# walter.net
KiCad netlist of a schematic drawn in EAGLE
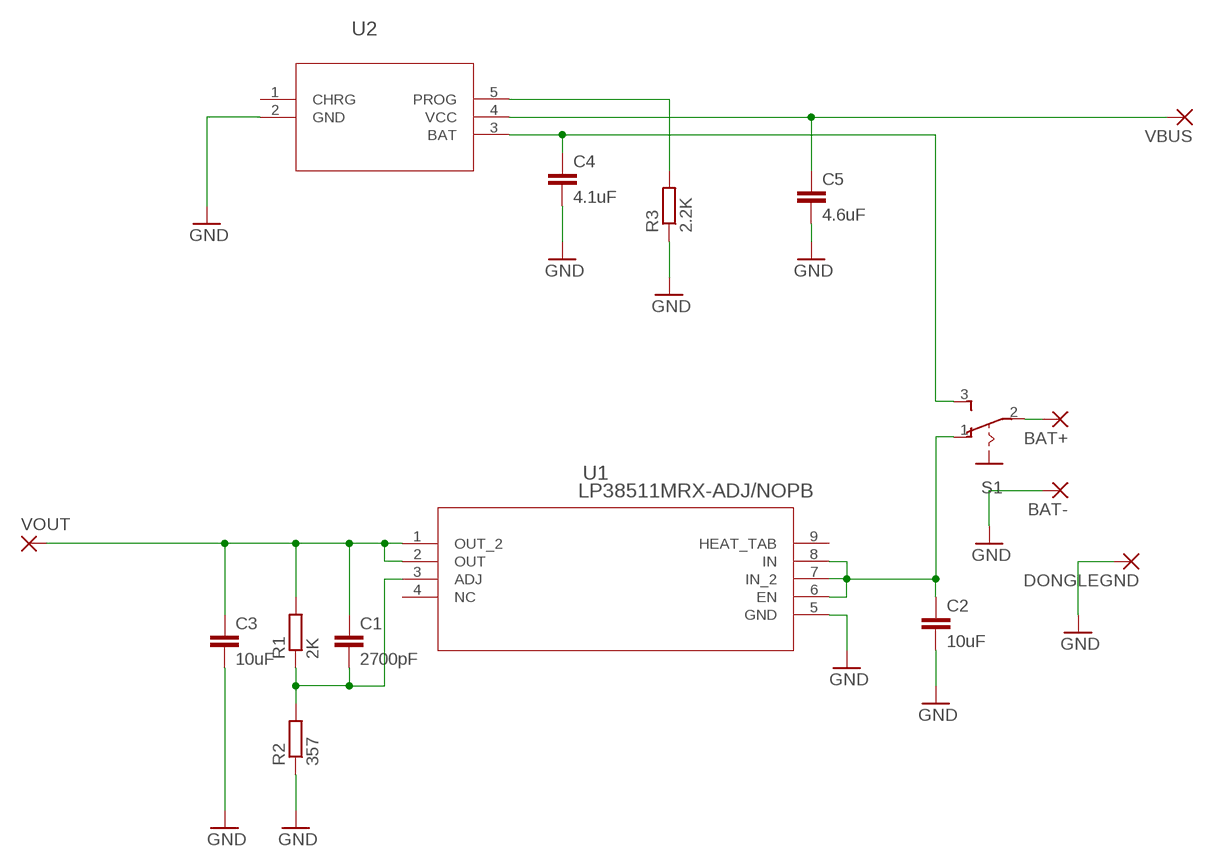
[diagram p0: schematic, sheet 1]

(export (version "E")
  (design (tool "Eeschema 10.0.6"))
  (components
    (comp (ref "BAT+")
      (value "1,6/0,8")
      (footprint "eagle-import:1,6_0,8")
      (libsource (lib "eagle-import") (part "1,6/0,8"))
    )
    (comp (ref "BAT-")
      (value "1,6/0,8")
      (footprint "eagle-import:1,6_0,8")
      (libsource (lib "eagle-import") (part "1,6/0,8"))
    )
    (comp (ref "C1")
      (value "2700pF")
      (footprint "eagle-import:C0402")
      (libsource (lib "eagle-import") (part "C-EUC0402"))
    )
    (comp (ref "C2")
      (value "10uF")
      (footprint "eagle-import:C0603")
      (libsource (lib "eagle-import") (part "C-EUC0603"))
    )
    (comp (ref "C3")
      (value "10uF")
      (footprint "eagle-import:C0603")
      (libsource (lib "eagle-import") (part "C-EUC0603"))
    )
    (comp (ref "C4")
      (value "4.1uF")
      (footprint "eagle-import:C0603")
      (libsource (lib "eagle-import") (part "C-EUC0603"))
    )
    (comp (ref "C5")
      (value "4.6uF")
      (footprint "eagle-import:C0603")
      (libsource (lib "eagle-import") (part "C-EUC0603"))
    )
    (comp (ref "DONGLEGND")
      (value "1,6/0,8")
      (footprint "eagle-import:1,6_0,8")
      (libsource (lib "eagle-import") (part "1,6/0,8"))
    )
    (comp (ref "R1")
      (value "2K")
      (footprint "eagle-import:R0402")
      (libsource (lib "eagle-import") (part "R-EU_R0402"))
    )
    (comp (ref "R2")
      (value "357")
      (footprint "eagle-import:R0603")
      (libsource (lib "eagle-import") (part "R-EU_R0603"))
    )
    (comp (ref "R3")
      (value "2.2K")
      (footprint "eagle-import:R0603")
      (libsource (lib "eagle-import") (part "R-EU_R0603"))
    )
    (comp (ref "S1")
      (value "255SB")
      (footprint "eagle-import:255SB")
      (libsource (lib "eagle-import") (part "255SB"))
    )
    (comp (ref "U1")
      (value "LP38511MRX-ADJ/NOPB")
      (footprint "eagle-import:MRA08B_TEX")
      (libsource (lib "eagle-import") (part "LP38511MRX-ADJ/NOPB"))
    )
    (comp (ref "U2")
      (value "LTC4054LES5-4.2TRPBF")
      (footprint "eagle-import:S_5_ADI")
      (fields
        (field (name "MANUFACTURER_PART_NUMBER") "LTC4054LES5-4.2#TRPBF")
        (field (name "COPYRIGHT") "Copyright (C) 2016 Accelerated Designs. All rights reserved")
      )
      (libsource (lib "eagle-import") (part "LTC4054LES5-4.2TRPBF"))
    )
    (comp (ref "VBUS")
      (value "1,6/0,8")
      (footprint "eagle-import:1,6_0,8")
      (libsource (lib "eagle-import") (part "1,6/0,8"))
    )
    (comp (ref "VOUT")
      (value "1,6/0,8")
      (footprint "eagle-import:1,6_0,8")
      (libsource (lib "eagle-import") (part "1,6/0,8"))
    )
  )
  (nets
    (net (code "1") (name "GND") (class "Default")
      (node (ref "BAT-") (pin "1") (pinfunction "P_1") (pintype "passive"))
      (node (ref "C2") (pin "2") (pinfunction "2_2") (pintype "passive"))
      (node (ref "C3") (pin "2") (pinfunction "2_2") (pintype "passive"))
      (node (ref "C4") (pin "2") (pinfunction "2_2") (pintype "passive"))
      (node (ref "C5") (pin "2") (pinfunction "2_2") (pintype "passive"))
      (node (ref "DONGLEGND") (pin "1") (pinfunction "P_1") (pintype "passive"))
      (node (ref "R2") (pin "1") (pinfunction "1_1") (pintype "passive"))
      (node (ref "R3") (pin "1") (pinfunction "1_1") (pintype "passive"))
      (node (ref "U1") (pin "5") (pinfunction "GND_5") (pintype "power_in"))
      (node (ref "U2") (pin "2") (pinfunction "GND_2") (pintype "passive"))
    )
    (net (code "2") (name "Net-(BAT+-P)") (class "Default")
      (node (ref "BAT+") (pin "1") (pinfunction "P_1") (pintype "passive"))
      (node (ref "S1") (pin "2") (pinfunction "P_2") (pintype "passive"))
    )
    (net (code "3") (name "Net-(S1-O)") (class "Default")
      (node (ref "C2") (pin "1") (pinfunction "1_1") (pintype "passive"))
      (node (ref "S1") (pin "1") (pinfunction "O_1") (pintype "passive"))
      (node (ref "U1") (pin "6") (pinfunction "EN_6") (pintype "input"))
      (node (ref "U1") (pin "7") (pinfunction "IN_2_7") (pintype "input"))
      (node (ref "U1") (pin "8") (pinfunction "IN_8") (pintype "input"))
    )
    (net (code "4") (name "Net-(S1-S)") (class "Default")
      (node (ref "C4") (pin "1") (pinfunction "1_1") (pintype "passive"))
      (node (ref "S1") (pin "3") (pinfunction "S_3") (pintype "passive"))
      (node (ref "U2") (pin "3") (pinfunction "BAT_3") (pintype "passive"))
    )
    (net (code "5") (name "Net-(U1-ADJ)") (class "Default")
      (node (ref "C1") (pin "2") (pinfunction "2_2") (pintype "passive"))
      (node (ref "R1") (pin "1") (pinfunction "1_1") (pintype "passive"))
      (node (ref "R2") (pin "2") (pinfunction "2_2") (pintype "passive"))
      (node (ref "U1") (pin "3") (pinfunction "ADJ_3") (pintype "passive"))
    )
    (net (code "6") (name "Net-(U1-OUT)") (class "Default")
      (node (ref "C1") (pin "1") (pinfunction "1_1") (pintype "passive"))
      (node (ref "C3") (pin "1") (pinfunction "1_1") (pintype "passive"))
      (node (ref "R1") (pin "2") (pinfunction "2_2") (pintype "passive"))
      (node (ref "U1") (pin "1") (pinfunction "OUT_2_1") (pintype "output"))
      (node (ref "U1") (pin "2") (pinfunction "OUT_2") (pintype "output"))
      (node (ref "VOUT") (pin "1") (pinfunction "P_1") (pintype "passive"))
    )
    (net (code "7") (name "Net-(U2-PROG)") (class "Default")
      (node (ref "R3") (pin "2") (pinfunction "2_2") (pintype "passive"))
      (node (ref "U2") (pin "5") (pinfunction "PROG_5") (pintype "passive"))
    )
    (net (code "8") (name "Net-(U2-VCC)") (class "Default")
      (node (ref "C5") (pin "1") (pinfunction "1_1") (pintype "passive"))
      (node (ref "U2") (pin "4") (pinfunction "VCC_4") (pintype "power_in"))
      (node (ref "VBUS") (pin "1") (pinfunction "P_1") (pintype "passive"))
    )
    (net (code "9") (name "unconnected-(U1-HEAT_TAB-Pad9)") (class "Default")
      (node (ref "U1") (pin "9") (pinfunction "HEAT_TAB_9") (pintype "passive"))
    )
    (net (code "10") (name "unconnected-(U1-NC-Pad4)") (class "Default")
      (node (ref "U1") (pin "4") (pinfunction "NC_4") (pintype "no_connect"))
    )
    (net (code "11") (name "unconnected-(U2-CHRG-Pad1)") (class "Default")
      (node (ref "U2") (pin "1") (pinfunction "CHRG_1") (pintype "passive"))
    )
  )
)
